# Sheet_1_2022-02-14.net
KiCad netlist of a schematic drawn in Altium Designer
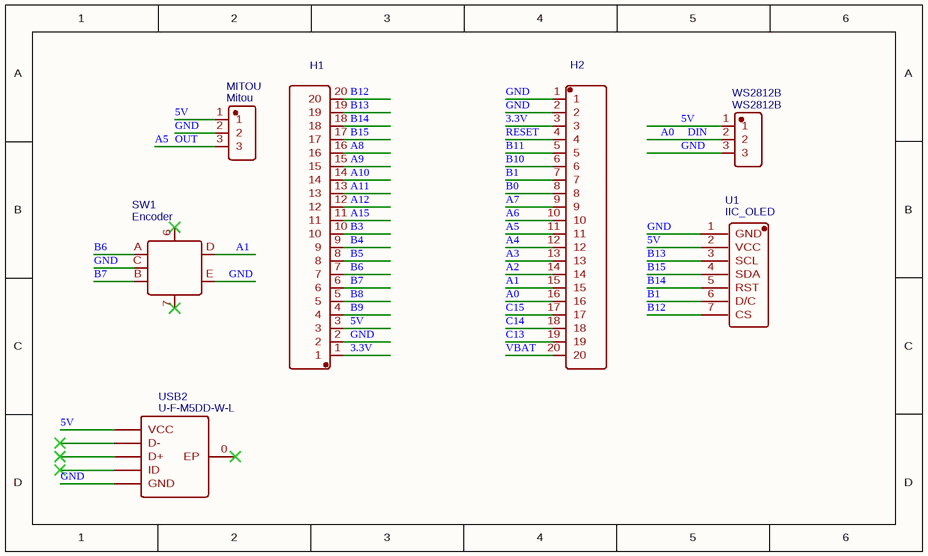
[diagram p0: Sheet_1_2022-02-14.schdoc]

(export (version "E")
  (design (tool "Eeschema 10.0.6"))
  (components
    (comp (ref "H1")
      (value "210S-1*20P L=11.6MMGold-plated black")
      (fields (field (name "BOM_SUPPLIER PART") "C124374") (field (name "CONTRIBUTOR") "LCSC"))
      (libsource (lib "altium-import") (part "root_2_210S-1*20P L=11.6MMGold-plated black_"))
    )
    (comp (ref "H2")
      (value "210S-1*20P L=11.6MMGold-plated black")
      (fields (field (name "BOM_SUPPLIER PART") "C124374") (field (name "CONTRIBUTOR") "LCSC"))
      (libsource (lib "altium-import") (part "root_0_210S-1*20P L=11.6MMGold-plated black_"))
    )
    (comp (ref "MITOU")
      (value "Mitou")
      (fields
        (field (name "BOM_MANUFACTURER PART") "Z-211-0311-0021-001")
        (field (name "BOM_SUPPLIER PART") "C152153")
        (field (name "CONTRIBUTOR") "LCSC")
      )
      (libsource (lib "altium-import") (part "root_0_Mitou_"))
    )
    (comp (ref "SW1")
      (value "Encoder")
      (fields
        (field (name "BOM_SUPPLIER PART") "C1322538")
        (field (name "BOM_MANUFACTURER PART") "EC11E09444A8")
        (field (name "CONTRIBUTOR") "LCSC")
      )
      (libsource (lib "altium-import") (part "root_3_Encoder_"))
    )
    (comp (ref "U1")
      (value "IIC_OLED")
      (fields (field (name "CONTRIBUTOR") "ccm1668447214"))
      (libsource (lib "altium-import") (part "root_0_IIC_OLED_"))
    )
    (comp (ref "USB2")
      (value "U-F-M5DD-W-L")
      (fields (field (name "BOM_SUPPLIER PART") "C145792") (field (name "CONTRIBUTOR") "LCSC"))
      (libsource (lib "altium-import") (part "root_0_U-F-M5DD-W-L_"))
    )
    (comp (ref "WS2812B")
      (value "WS2812B")
      (fields
        (field (name "BOM_MANUFACTURER PART") "Z-211-0311-0021-001")
        (field (name "BOM_SUPPLIER PART") "C152153")
        (field (name "CONTRIBUTOR") "LCSC")
      )
      (libsource (lib "altium-import") (part "root_0_WS2812B_"))
    )
  )
  (nets
    (net (code "1") (name "/3.3V") (class "Default")
      (node (ref "H1") (pin "1") (pinfunction "1_1") (pintype "passive"))
      (node (ref "H2") (pin "3") (pinfunction "3_3") (pintype "passive"))
    )
    (net (code "2") (name "/5V") (class "Default")
      (node (ref "H1") (pin "3") (pinfunction "3_3") (pintype "passive"))
      (node (ref "MITOU") (pin "1") (pinfunction "1_1") (pintype "passive"))
      (node (ref "U1") (pin "2") (pinfunction "VCC_2") (pintype "passive"))
      (node (ref "USB2") (pin "1") (pinfunction "VCC_1") (pintype "passive"))
      (node (ref "WS2812B") (pin "1") (pinfunction "1_1") (pintype "passive"))
    )
    (net (code "3") (name "/A0") (class "Default")
      (node (ref "H2") (pin "16") (pinfunction "16_16") (pintype "passive"))
      (node (ref "WS2812B") (pin "2") (pinfunction "2_2") (pintype "passive"))
    )
    (net (code "4") (name "/A1") (class "Default")
      (node (ref "H2") (pin "15") (pinfunction "15_15") (pintype "passive"))
      (node (ref "SW1") (pin "D") (pinfunction "D_D") (pintype "passive"))
    )
    (net (code "5") (name "/A2") (class "Default")
      (node (ref "H2") (pin "14") (pinfunction "14_14") (pintype "passive"))
    )
    (net (code "6") (name "/A3") (class "Default")
      (node (ref "H2") (pin "13") (pinfunction "13_13") (pintype "passive"))
    )
    (net (code "7") (name "/A4") (class "Default")
      (node (ref "H2") (pin "12") (pinfunction "12_12") (pintype "passive"))
    )
    (net (code "8") (name "/A5") (class "Default")
      (node (ref "H2") (pin "11") (pinfunction "11_11") (pintype "passive"))
      (node (ref "MITOU") (pin "3") (pinfunction "3_3") (pintype "passive"))
    )
    (net (code "9") (name "/A6") (class "Default")
      (node (ref "H2") (pin "10") (pinfunction "10_10") (pintype "passive"))
    )
    (net (code "10") (name "/A7") (class "Default")
      (node (ref "H2") (pin "9") (pinfunction "9_9") (pintype "passive"))
    )
    (net (code "11") (name "/A8") (class "Default")
      (node (ref "H1") (pin "16") (pinfunction "16_16") (pintype "passive"))
    )
    (net (code "12") (name "/A9") (class "Default")
      (node (ref "H1") (pin "15") (pinfunction "15_15") (pintype "passive"))
    )
    (net (code "13") (name "/A10") (class "Default")
      (node (ref "H1") (pin "14") (pinfunction "14_14") (pintype "passive"))
    )
    (net (code "14") (name "/A11") (class "Default")
      (node (ref "H1") (pin "13") (pinfunction "13_13") (pintype "passive"))
    )
    (net (code "15") (name "/A12") (class "Default")
      (node (ref "H1") (pin "12") (pinfunction "12_12") (pintype "passive"))
    )
    (net (code "16") (name "/A15") (class "Default")
      (node (ref "H1") (pin "11") (pinfunction "11_11") (pintype "passive"))
    )
    (net (code "17") (name "/B0") (class "Default")
      (node (ref "H2") (pin "8") (pinfunction "8_8") (pintype "passive"))
    )
    (net (code "18") (name "/B1") (class "Default")
      (node (ref "H2") (pin "7") (pinfunction "7_7") (pintype "passive"))
      (node (ref "U1") (pin "6") (pinfunction "D/C_6") (pintype "passive"))
    )
    (net (code "19") (name "/B3") (class "Default")
      (node (ref "H1") (pin "10") (pinfunction "10_10") (pintype "passive"))
    )
    (net (code "20") (name "/B4") (class "Default")
      (node (ref "H1") (pin "9") (pinfunction "9_9") (pintype "passive"))
    )
    (net (code "21") (name "/B5") (class "Default")
      (node (ref "H1") (pin "8") (pinfunction "8_8") (pintype "passive"))
    )
    (net (code "22") (name "/B6") (class "Default")
      (node (ref "H1") (pin "7") (pinfunction "7_7") (pintype "passive"))
      (node (ref "SW1") (pin "A") (pinfunction "A_A") (pintype "passive"))
    )
    (net (code "23") (name "/B7") (class "Default")
      (node (ref "H1") (pin "6") (pinfunction "6_6") (pintype "passive"))
      (node (ref "SW1") (pin "B") (pinfunction "B_B") (pintype "passive"))
    )
    (net (code "24") (name "/B8") (class "Default")
      (node (ref "H1") (pin "5") (pinfunction "5_5") (pintype "passive"))
    )
    (net (code "25") (name "/B9") (class "Default")
      (node (ref "H1") (pin "4") (pinfunction "4_4") (pintype "passive"))
    )
    (net (code "26") (name "/B10") (class "Default")
      (node (ref "H2") (pin "6") (pinfunction "6_6") (pintype "passive"))
    )
    (net (code "27") (name "/B11") (class "Default")
      (node (ref "H2") (pin "5") (pinfunction "5_5") (pintype "passive"))
    )
    (net (code "28") (name "/B12") (class "Default")
      (node (ref "H1") (pin "20") (pinfunction "20_20") (pintype "passive"))
      (node (ref "U1") (pin "7") (pinfunction "CS_7") (pintype "passive"))
    )
    (net (code "29") (name "/B13") (class "Default")
      (node (ref "H1") (pin "19") (pinfunction "19_19") (pintype "passive"))
      (node (ref "U1") (pin "3") (pinfunction "SCL_3") (pintype "passive"))
    )
    (net (code "30") (name "/B14") (class "Default")
      (node (ref "H1") (pin "18") (pinfunction "18_18") (pintype "passive"))
      (node (ref "U1") (pin "5") (pinfunction "RST_5") (pintype "passive"))
    )
    (net (code "31") (name "/B15") (class "Default")
      (node (ref "H1") (pin "17") (pinfunction "17_17") (pintype "passive"))
      (node (ref "U1") (pin "4") (pinfunction "SDA_4") (pintype "passive"))
    )
    (net (code "32") (name "/C13") (class "Default")
      (node (ref "H2") (pin "19") (pinfunction "19_19") (pintype "passive"))
    )
    (net (code "33") (name "/C14") (class "Default")
      (node (ref "H2") (pin "18") (pinfunction "18_18") (pintype "passive"))
    )
    (net (code "34") (name "/C15") (class "Default")
      (node (ref "H2") (pin "17") (pinfunction "17_17") (pintype "passive"))
    )
    (net (code "35") (name "/GND") (class "Default")
      (node (ref "H1") (pin "2") (pinfunction "2_2") (pintype "passive"))
      (node (ref "H2") (pin "1") (pinfunction "1_1") (pintype "passive"))
      (node (ref "H2") (pin "2") (pinfunction "2_2") (pintype "passive"))
      (node (ref "MITOU") (pin "2") (pinfunction "2_2") (pintype "passive"))
      (node (ref "SW1") (pin "C") (pinfunction "C_C") (pintype "passive"))
      (node (ref "SW1") (pin "E") (pinfunction "E_E") (pintype "passive"))
      (node (ref "U1") (pin "1") (pinfunction "GND_1") (pintype "passive"))
      (node (ref "USB2") (pin "5") (pinfunction "GND_5") (pintype "passive"))
      (node (ref "WS2812B") (pin "3") (pinfunction "3_3") (pintype "passive"))
    )
    (net (code "36") (name "/RESET") (class "Default")
      (node (ref "H2") (pin "4") (pinfunction "4_4") (pintype "passive"))
    )
    (net (code "37") (name "/VBAT") (class "Default")
      (node (ref "H2") (pin "20") (pinfunction "20_20") (pintype "passive"))
    )
    (net (code "38") (name "unconnected-(SW1-EH-Pad6)") (class "Default")
      (node (ref "SW1") (pin "6") (pinfunction "EH_6") (pintype "passive+no_connect"))
    )
    (net (code "39") (name "unconnected-(SW1-EH-Pad7)") (class "Default")
      (node (ref "SW1") (pin "7") (pinfunction "EH_7") (pintype "passive+no_connect"))
    )
    (net (code "40") (name "unconnected-(USB2-D+-Pad3)") (class "Default")
      (node (ref "USB2") (pin "3") (pinfunction "D+_3") (pintype "passive+no_connect"))
    )
    (net (code "41") (name "unconnected-(USB2-D--Pad2)") (class "Default")
      (node (ref "USB2") (pin "2") (pinfunction "D-_2") (pintype "passive+no_connect"))
    )
    (net (code "42") (name "unconnected-(USB2-EP-Pad0)") (class "Default")
      (node (ref "USB2") (pin "0") (pinfunction "EP_0") (pintype "passive+no_connect"))
    )
    (net (code "43") (name "unconnected-(USB2-ID-Pad4)") (class "Default")
      (node (ref "USB2") (pin "4") (pinfunction "ID_4") (pintype "passive+no_connect"))
    )
  )
)
